# USB-TYPEC_CON.net
KiCad netlist of a schematic drawn in Altium Designer
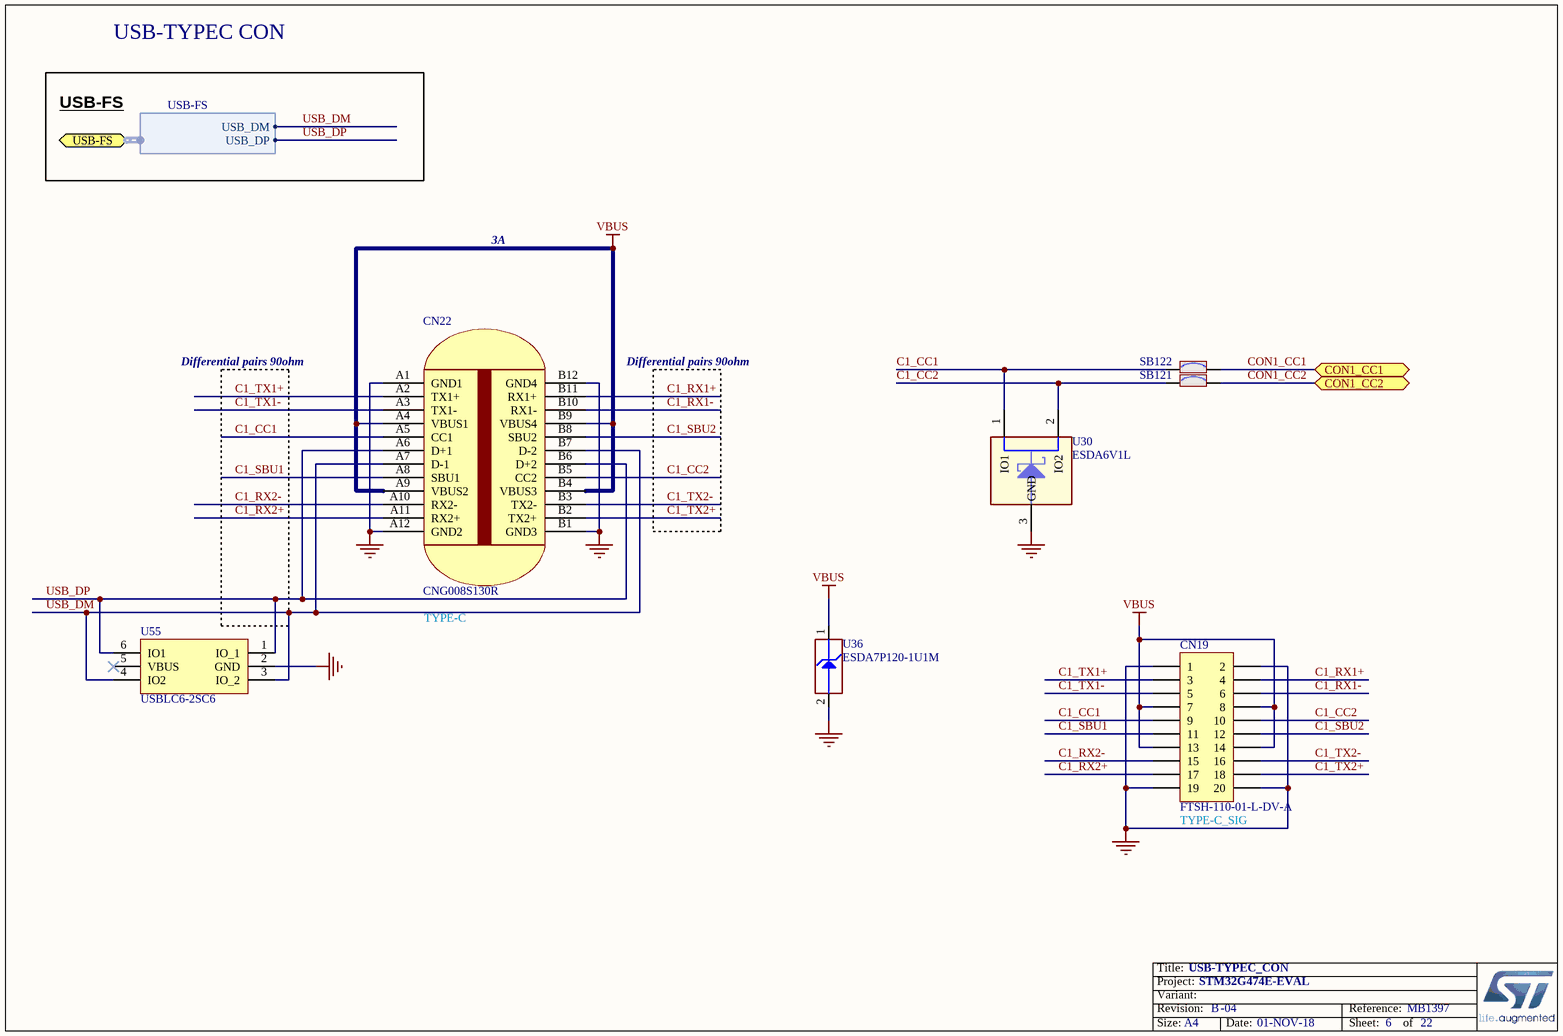
[diagram p0: USB-TYPEC_CON.SchDoc]

(export (version "E")
  (design (tool "Eeschema 10.0.6"))
  (components
    (comp (ref "CN19")
      (value "FTSH-110-01-L-DV-A")
      (footprint "CON_SAMTEC_FTSH-110-01-L-DV-A")
      (description "Header 10x2, 1.27mm, VR, CMS, Height 3.05mm with alignment pin")
      (fields
        (field (name "INTERNAL_PART_NUMBER") "MCD-01561")
        (field (name "MANUFACTURER") "SAMTEC")
        (field (name "PROVIDED_BY") "SUBCO")
      )
      (libsource (lib "MCD_PARTS_database") (part "Header 10x2"))
    )
    (comp (ref "CN22")
      (value "CNG008S130R")
      (footprint "CON_USB-TYPEC_LITKCONN-TECHNOLOGY_CNG008S130R")
      (description "USB Type C certified Connector SMT Mid-mount")
      (fields
        (field (name "INTERNAL_PART_NUMBER") "MCD-00678")
        (field (name "MANUFACTURER") "LITKCON TECHNOLOGY")
        (field (name "PROVIDED_BY") "SUBCO")
      )
      (libsource (lib "MCD_PARTS_database") (part "USB Type-C"))
    )
    (comp (ref "SB121")
      (value "SB_ON")
      (footprint "SOLDER-BRIDGE_R0603-0R")
      (description "Solder Bridge ON")
      (fields
        (field (name "INTERNAL_PART_NUMBER") "MCD-00071")
        (field (name "MANUFACTURER_PART_NUMBER") "RC0603JR-070RL")
        (field (name "PROVIDED_BY") "SUBCO")
      )
      (libsource (lib "MCD_PARTS_database") (part "SB_ON"))
    )
    (comp (ref "SB122")
      (value "SB_ON")
      (footprint "SOLDER-BRIDGE_R0603-0R")
      (description "Solder Bridge ON")
      (fields
        (field (name "INTERNAL_PART_NUMBER") "MCD-00071")
        (field (name "MANUFACTURER_PART_NUMBER") "RC0603JR-070RL")
        (field (name "PROVIDED_BY") "SUBCO")
      )
      (libsource (lib "MCD_PARTS_database") (part "SB_ON"))
    )
    (comp (ref "U30")
      (value "ESDA6V1L")
      (footprint "ESD_SOT23")
      (description "Dual Transil array ESD protection")
      (fields
        (field (name "INTERNAL_PART_NUMBER") "MCD-00255")
        (field (name "MANUFACTURER") "STMICROELECTRONICS")
        (field (name "PROVIDED_BY") "SUBCO with ST control")
      )
      (libsource (lib "MCD_PARTS_database") (part "ESDAxxL"))
    )
    (comp (ref "U36")
      (value "ESDA7P120-1U1M")
      (footprint "ESD_QFN1610_2N_1K_2A")
      (description "High power transient voltage suppressor")
      (fields
        (field (name "INTERNAL_PART_NUMBER") "MCD-01026")
        (field (name "MANUFACTURER") "STMICROELECTRONICS")
        (field (name "PROVIDED_BY") "SUBCO with ST control")
      )
      (libsource (lib "MCD_PARTS_database") (part "ESD-TRANSIL"))
    )
    (comp (ref "U55")
      (value "USBLC6-2SC6")
      (footprint "ESD_SOT23-6L")
      (description "Very low capacitance ESD protection")
      (fields
        (field (name "INTERNAL_PART_NUMBER") "MCD-00163")
        (field (name "MANUFACTURER") "STMICROELECTRONICS")
        (field (name "PROVIDED_BY") "SUBCO with ST control")
      )
      (libsource (lib "MCD_PARTS_database") (part "USBLC6-2SC6"))
    )
  )
  (nets
    (net (code "2") (name "/C1_CC1") (class "Default")
      (node (ref "CN19") (pin "9") (pinfunction "9_9") (pintype "passive"))
      (node (ref "CN22") (pin "A5") (pinfunction "CC1_A5") (pintype "passive"))
      (node (ref "SB122") (pin "1") (pinfunction "1_1") (pintype "passive"))
      (node (ref "U30") (pin "1") (pinfunction "IO1_1") (pintype "passive"))
    )
    (net (code "3") (name "/C1_CC2") (class "Default")
      (node (ref "CN19") (pin "10") (pinfunction "10_10") (pintype "passive"))
      (node (ref "CN22") (pin "B5") (pinfunction "CC2_B5") (pintype "passive"))
      (node (ref "SB121") (pin "1") (pinfunction "1_1") (pintype "passive"))
      (node (ref "U30") (pin "2") (pinfunction "IO2_2") (pintype "passive"))
    )
    (net (code "4") (name "/C1_RX1+") (class "Default")
      (node (ref "CN19") (pin "4") (pinfunction "4_4") (pintype "passive"))
      (node (ref "CN22") (pin "B11") (pinfunction "RX1+_B11") (pintype "passive"))
    )
    (net (code "5") (name "/C1_RX1-") (class "Default")
      (node (ref "CN19") (pin "6") (pinfunction "6_6") (pintype "passive"))
      (node (ref "CN22") (pin "B10") (pinfunction "RX1-_B10") (pintype "passive"))
    )
    (net (code "6") (name "/C1_RX2+") (class "Default")
      (node (ref "CN19") (pin "17") (pinfunction "17_17") (pintype "passive"))
      (node (ref "CN22") (pin "A11") (pinfunction "RX2+_A11") (pintype "passive"))
    )
    (net (code "7") (name "/C1_RX2-") (class "Default")
      (node (ref "CN19") (pin "15") (pinfunction "15_15") (pintype "passive"))
      (node (ref "CN22") (pin "A10") (pinfunction "RX2-_A10") (pintype "passive"))
    )
    (net (code "8") (name "/C1_SBU1") (class "Default")
      (node (ref "CN19") (pin "11") (pinfunction "11_11") (pintype "passive"))
      (node (ref "CN22") (pin "A8") (pinfunction "SBU1_A8") (pintype "passive"))
    )
    (net (code "9") (name "/C1_SBU2") (class "Default")
      (node (ref "CN19") (pin "12") (pinfunction "12_12") (pintype "passive"))
      (node (ref "CN22") (pin "B8") (pinfunction "SBU2_B8") (pintype "passive"))
    )
    (net (code "10") (name "/C1_TX1+") (class "Default")
      (node (ref "CN19") (pin "3") (pinfunction "3_3") (pintype "passive"))
      (node (ref "CN22") (pin "A2") (pinfunction "TX1+_A2") (pintype "passive"))
    )
    (net (code "11") (name "/C1_TX1-") (class "Default")
      (node (ref "CN19") (pin "5") (pinfunction "5_5") (pintype "passive"))
      (node (ref "CN22") (pin "A3") (pinfunction "TX1-_A3") (pintype "passive"))
    )
    (net (code "12") (name "/C1_TX2+") (class "Default")
      (node (ref "CN19") (pin "18") (pinfunction "18_18") (pintype "passive"))
      (node (ref "CN22") (pin "B2") (pinfunction "TX2+_B2") (pintype "passive"))
    )
    (net (code "13") (name "/C1_TX2-") (class "Default")
      (node (ref "CN19") (pin "16") (pinfunction "16_16") (pintype "passive"))
      (node (ref "CN22") (pin "B3") (pinfunction "TX2-_B3") (pintype "passive"))
    )
    (net (code "14") (name "/CON1_CC1") (class "Default")
      (node (ref "SB122") (pin "2") (pinfunction "2_2") (pintype "passive"))
    )
    (net (code "15") (name "/CON1_CC2") (class "Default")
      (node (ref "SB121") (pin "2") (pinfunction "2_2") (pintype "passive"))
    )
    (net (code "16") (name "/USB_DM") (class "Default")
      (node (ref "CN22") (pin "A7") (pinfunction "D-1_A7") (pintype "passive"))
      (node (ref "CN22") (pin "B7") (pinfunction "D-2_B7") (pintype "passive"))
      (node (ref "U55") (pin "3") (pinfunction "IO_2_3") (pintype "passive"))
      (node (ref "U55") (pin "4") (pinfunction "IO2_4") (pintype "passive"))
    )
    (net (code "17") (name "/USB_DP") (class "Default")
      (node (ref "CN22") (pin "A6") (pinfunction "D+1_A6") (pintype "passive"))
      (node (ref "CN22") (pin "B6") (pinfunction "D+2_B6") (pintype "passive"))
      (node (ref "U55") (pin "1") (pinfunction "IO_1_1") (pintype "passive"))
      (node (ref "U55") (pin "6") (pinfunction "IO1_6") (pintype "passive"))
    )
    (net (code "19") (name "GND") (class "Default")
      (node (ref "CN19") (pin "1") (pinfunction "1_1") (pintype "passive"))
      (node (ref "CN19") (pin "19") (pinfunction "19_19") (pintype "passive"))
      (node (ref "CN19") (pin "2") (pinfunction "2_2") (pintype "passive"))
      (node (ref "CN19") (pin "20") (pinfunction "20_20") (pintype "passive"))
      (node (ref "CN22") (pin "A1") (pinfunction "GND1_A1") (pintype "passive"))
      (node (ref "CN22") (pin "A12") (pinfunction "GND2_A12") (pintype "passive"))
      (node (ref "CN22") (pin "B1") (pinfunction "GND3_B1") (pintype "passive"))
      (node (ref "CN22") (pin "B12") (pinfunction "GND4_B12") (pintype "passive"))
      (node (ref "U30") (pin "3") (pinfunction "GND_3") (pintype "passive"))
      (node (ref "U36") (pin "2") (pinfunction "GND_2") (pintype "passive"))
      (node (ref "U55") (pin "2") (pinfunction "GND_2") (pintype "passive"))
    )
    (net (code "20") (name "VBUS") (class "Default")
      (node (ref "CN19") (pin "13") (pinfunction "13_13") (pintype "passive"))
      (node (ref "CN19") (pin "14") (pinfunction "14_14") (pintype "passive"))
      (node (ref "CN19") (pin "7") (pinfunction "7_7") (pintype "passive"))
      (node (ref "CN19") (pin "8") (pinfunction "8_8") (pintype "passive"))
      (node (ref "CN22") (pin "A4") (pinfunction "VBUS1_A4") (pintype "passive"))
      (node (ref "CN22") (pin "A9") (pinfunction "VBUS2_A9") (pintype "passive"))
      (node (ref "CN22") (pin "B4") (pinfunction "VBUS3_B4") (pintype "passive"))
      (node (ref "CN22") (pin "B9") (pinfunction "VBUS4_B9") (pintype "passive"))
      (node (ref "U36") (pin "1") (pinfunction "IO1_1") (pintype "passive"))
    )
    (net (code "21") (name "unconnected-(U55-VBUS-Pad5)") (class "Default")
      (node (ref "U55") (pin "5") (pinfunction "VBUS_5") (pintype "passive+no_connect"))
    )
  )
)
